# Microcontroller.net
KiCad netlist of a schematic drawn in Altium Designer
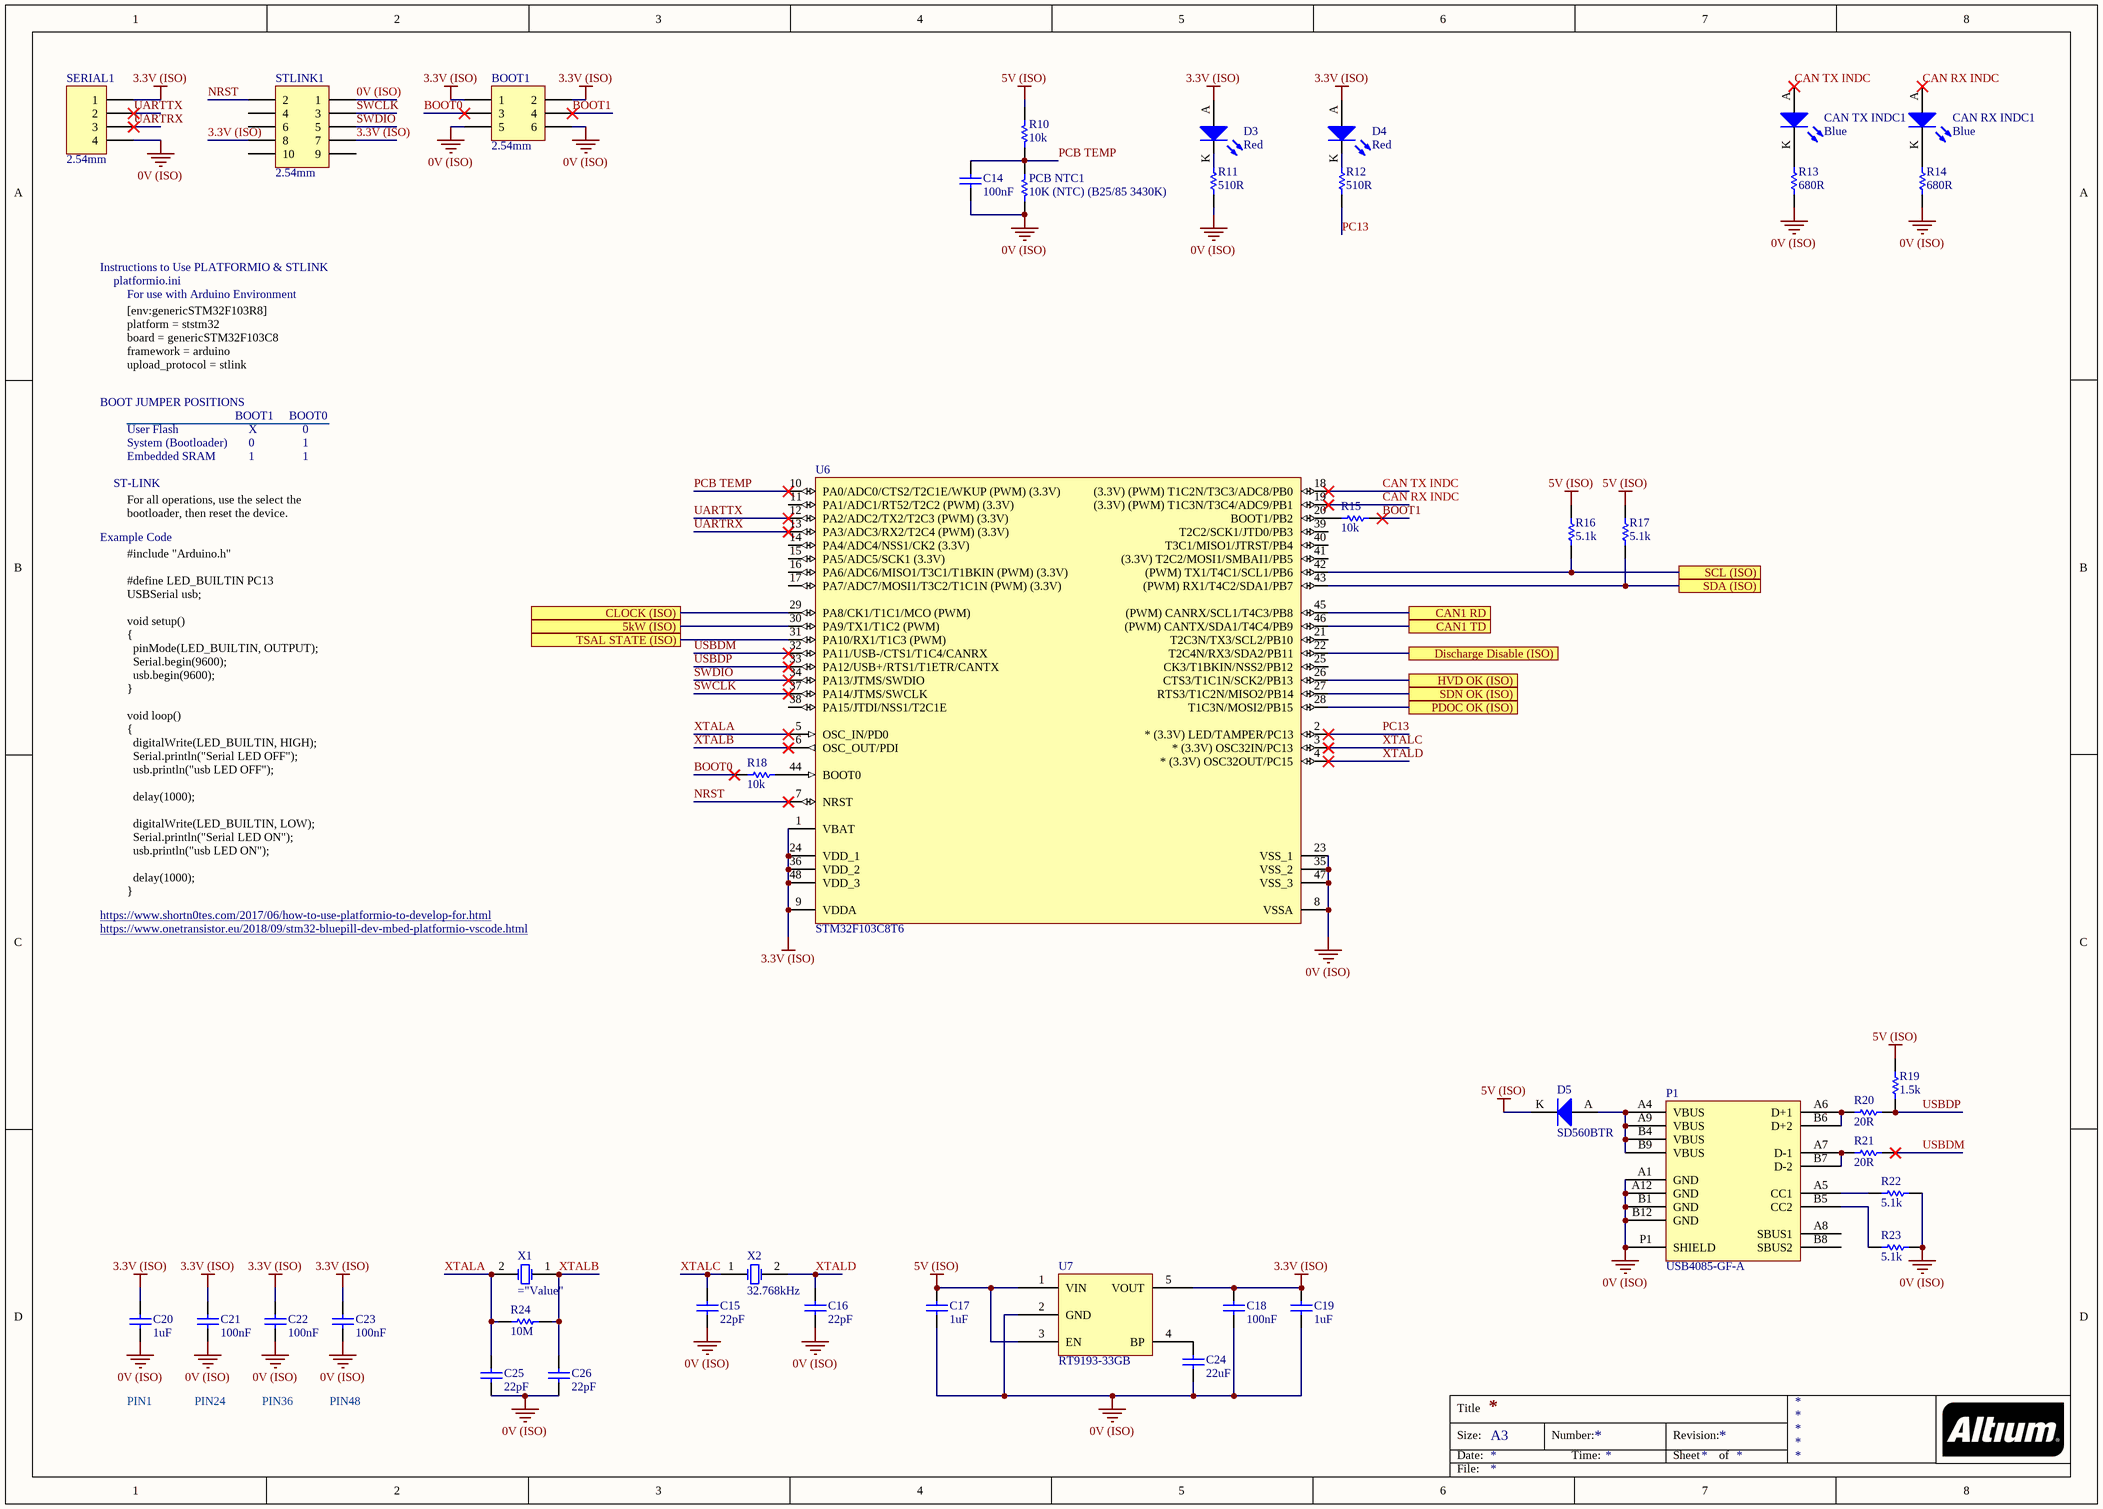
[diagram p0: Microcontroller.SchDoc]

(export (version "E")
  (design (tool "Eeschema 10.0.6"))
  (components
    (comp (ref "BOOT1")
      (value "2.54mm")
      (footprint "TH 2.54mm Header 2x3")
      (fields (field (name "PART NUMBER") "TH 2.54mm Header 2x3") (field (name "CONTACT") "NA"))
      (libsource (lib "ts_20-standard-connectors") (part "Header 2x3"))
    )
    (comp (ref "C14")
      (value "100nF")
      (footprint "0805")
      (fields
        (field (name "PART NUMBER") "GCM21BR71E104KA37L")
        (field (name "TOLERANCE") "10%")
        (field (name "MANUFACTURER") "muRata")
      )
      (libsource (lib "ts_20-standard-library") (part "Capacitor"))
    )
    (comp (ref "C15")
      (value "22pF")
      (footprint "0805")
      (fields
        (field (name "PART NUMBER") "GCM21B5C1H220JA37L")
        (field (name "TOLERANCE") "5%")
        (field (name "MANUFACTURER") "muRata")
      )
      (libsource (lib "ts_20-standard-library") (part "Capacitor"))
    )
    (comp (ref "C16")
      (value "22pF")
      (footprint "0805")
      (fields
        (field (name "PART NUMBER") "GCM21B5C1H220JA37L")
        (field (name "TOLERANCE") "5%")
        (field (name "MANUFACTURER") "muRata")
      )
      (libsource (lib "ts_20-standard-library") (part "Capacitor"))
    )
    (comp (ref "C17")
      (value "1uF")
      (footprint "0805")
      (fields
        (field (name "PART NUMBER") "AC0805KKX7R8BB105")
        (field (name "TOLERANCE") "10%")
        (field (name "MANUFACTURER") "YAGEO")
      )
      (libsource (lib "ts_20-standard-library") (part "Capacitor"))
    )
    (comp (ref "C18")
      (value "100nF")
      (footprint "0805")
      (fields
        (field (name "PART NUMBER") "GCM21BR71E104KA37L")
        (field (name "TOLERANCE") "10%")
        (field (name "MANUFACTURER") "muRata")
      )
      (libsource (lib "ts_20-standard-library") (part "Capacitor"))
    )
    (comp (ref "C19")
      (value "1uF")
      (footprint "0805")
      (fields
        (field (name "PART NUMBER") "AC0805KKX7R8BB105")
        (field (name "TOLERANCE") "10%")
        (field (name "MANUFACTURER") "YAGEO")
      )
      (libsource (lib "ts_20-standard-library") (part "Capacitor"))
    )
    (comp (ref "C20")
      (value "1uF")
      (footprint "0805")
      (fields
        (field (name "PART NUMBER") "AC0805KKX7R8BB105")
        (field (name "TOLERANCE") "10%")
        (field (name "MANUFACTURER") "YAGEO")
      )
      (libsource (lib "ts_20-standard-library") (part "Capacitor"))
    )
    (comp (ref "C21")
      (value "100nF")
      (footprint "0805")
      (fields
        (field (name "PART NUMBER") "GCM21BR71E104KA37L")
        (field (name "TOLERANCE") "10%")
        (field (name "MANUFACTURER") "muRata")
      )
      (libsource (lib "ts_20-standard-library") (part "Capacitor"))
    )
    (comp (ref "C22")
      (value "100nF")
      (footprint "0805")
      (fields
        (field (name "PART NUMBER") "GCM21BR71E104KA37L")
        (field (name "TOLERANCE") "10%")
        (field (name "MANUFACTURER") "muRata")
      )
      (libsource (lib "ts_20-standard-library") (part "Capacitor"))
    )
    (comp (ref "C23")
      (value "100nF")
      (footprint "0805")
      (fields
        (field (name "PART NUMBER") "GCM21BR71E104KA37L")
        (field (name "TOLERANCE") "10%")
        (field (name "MANUFACTURER") "muRata")
      )
      (libsource (lib "ts_20-standard-library") (part "Capacitor"))
    )
    (comp (ref "C24")
      (value "22uF")
      (footprint "0805")
      (fields
        (field (name "PART NUMBER") "GRM21BR61A226ME51L")
        (field (name "TOLERANCE") "20%")
        (field (name "MANUFACTURER") "muRata")
      )
      (libsource (lib "ts_20-standard-library") (part "Capacitor"))
    )
    (comp (ref "C25")
      (value "22pF")
      (footprint "0805")
      (fields
        (field (name "PART NUMBER") "GCM21B5C1H220JA37L")
        (field (name "TOLERANCE") "5%")
        (field (name "MANUFACTURER") "muRata")
      )
      (libsource (lib "ts_20-standard-library") (part "Capacitor"))
    )
    (comp (ref "C26")
      (value "22pF")
      (footprint "0805")
      (fields
        (field (name "PART NUMBER") "GCM21B5C1H220JA37L")
        (field (name "TOLERANCE") "5%")
        (field (name "MANUFACTURER") "muRata")
      )
      (libsource (lib "ts_20-standard-library") (part "Capacitor"))
    )
    (comp (ref "CAN RX INDC1")
      (value "Blue")
      (footprint "0805 LED")
      (description "LED BLUE CLEAR 2012 SMD")
      (fields
        (field (name "PART NUMBER") "SML-MN2BCTT86C")
        (field (name "MANUFACTURER") "ROHM Semiconductor")
      )
      (libsource (lib "ts_20-standard-library") (part "LED"))
    )
    (comp (ref "CAN TX INDC1")
      (value "Blue")
      (footprint "0805 LED")
      (description "LED BLUE CLEAR 2012 SMD")
      (fields
        (field (name "PART NUMBER") "SML-MN2BCTT86C")
        (field (name "MANUFACTURER") "ROHM Semiconductor")
      )
      (libsource (lib "ts_20-standard-library") (part "LED"))
    )
    (comp (ref "D3")
      (value "Red")
      (footprint "0805 LED")
      (description "Red LED Indication - Discrete 1.75V 0805 (2012 Metric)")
      (fields (field (name "MANUFACTURER") "ROHM Semiconductor") (field (name "PART NUMBER") "SML-210LTT86"))
      (libsource (lib "ts_20-standard-library") (part "LED"))
    )
    (comp (ref "D4")
      (value "Red")
      (footprint "0805 LED")
      (description "Red LED Indication - Discrete 1.75V 0805 (2012 Metric)")
      (fields (field (name "MANUFACTURER") "ROHM Semiconductor") (field (name "PART NUMBER") "SML-210LTT86"))
      (libsource (lib "ts_20-standard-library") (part "LED"))
    )
    (comp (ref "D5")
      (value "SD560BTR")
      (footprint "SMB Diode")
      (description "1.2V_F 600V 5A SMB")
      (fields
        (field (name "MANUFACTURER") "SMC Diode Solutions")
        (field (name "DIGIKEY PART NUMBER") "1655-1530-2-ND")
      )
      (libsource (lib "ts_20-standard-library") (part "Diode"))
    )
    (comp (ref "P1")
      (value "USB4085-GF-A")
      (footprint "USB4085-GF-A")
      (description "USB - C (Type - C) USB 2.0 Receptacle Connector 16 Position Through Hole, Right Angle")
      (fields (field (name "DIGIKEY PART NUMBER") "2073-USB4085-GF-ACT-ND"))
      (libsource (lib "ts_20-standard-connectors") (part "USB4085-GF-A"))
    )
    (comp (ref "PCB NTC1")
      (value "10K (NTC) (B25/85 3430K)")
      (footprint "0805")
      (fields
        (field (name "PART NUMBER") "NTCS0805E3103FLT")
        (field (name "MANUFACTURER") "Vishay Beyschlag")
        (field (name "TOLERANCE") "0.01")
      )
      (libsource (lib "ts_20-standard-library") (part "Resistor"))
    )
    (comp (ref "R10")
      (value "10k")
      (footprint "0805")
      (fields
        (field (name "PART NUMBER") "RC0805FR0710KL")
        (field (name "MANUFACTURER") "YAGEO")
        (field (name "TOLERANCE") "0.01")
      )
      (libsource (lib "ts_20-standard-library") (part "Resistor"))
    )
    (comp (ref "R11")
      (value "510R")
      (footprint "0805")
      (fields
        (field (name "MANUFACTURER") "YAGEO")
        (field (name "PART NUMBER") "RC0805FR07510RL")
        (field (name "TOLERANCE") "0.01")
      )
      (libsource (lib "ts_20-standard-library") (part "Resistor"))
    )
    (comp (ref "R12")
      (value "510R")
      (footprint "0805")
      (fields
        (field (name "MANUFACTURER") "YAGEO")
        (field (name "PART NUMBER") "RC0805FR07510RL")
        (field (name "TOLERANCE") "0.01")
      )
      (libsource (lib "ts_20-standard-library") (part "Resistor"))
    )
    (comp (ref "R13")
      (value "680R")
      (footprint "0805")
      (fields
        (field (name "PART NUMBER") "RC0805FR07680RL")
        (field (name "MANUFACTURER") "YAGEO")
        (field (name "TOLERANCE") "0.01")
      )
      (libsource (lib "ts_20-standard-library") (part "Resistor"))
    )
    (comp (ref "R14")
      (value "680R")
      (footprint "0805")
      (fields
        (field (name "PART NUMBER") "RC0805FR07680RL")
        (field (name "MANUFACTURER") "YAGEO")
        (field (name "TOLERANCE") "0.01")
      )
      (libsource (lib "ts_20-standard-library") (part "Resistor"))
    )
    (comp (ref "R15")
      (value "10k")
      (footprint "0805")
      (fields
        (field (name "PART NUMBER") "RC0805FR0710KL")
        (field (name "MANUFACTURER") "YAGEO")
        (field (name "TOLERANCE") "0.01")
      )
      (libsource (lib "ts_20-standard-library") (part "Resistor"))
    )
    (comp (ref "R16")
      (value "5.1k")
      (footprint "0805")
      (fields
        (field (name "PART NUMBER") "RC0805FR075K1L")
        (field (name "MANUFACTURER") "YAGEO")
        (field (name "TOLERANCE") "0.01")
      )
      (libsource (lib "ts_20-standard-library") (part "Resistor"))
    )
    (comp (ref "R17")
      (value "5.1k")
      (footprint "0805")
      (fields
        (field (name "PART NUMBER") "RC0805FR075K1L")
        (field (name "MANUFACTURER") "YAGEO")
        (field (name "TOLERANCE") "0.01")
      )
      (libsource (lib "ts_20-standard-library") (part "Resistor"))
    )
    (comp (ref "R18")
      (value "10k")
      (footprint "0805")
      (fields
        (field (name "PART NUMBER") "RC0805FR0710KL")
        (field (name "MANUFACTURER") "YAGEO")
        (field (name "TOLERANCE") "0.01")
      )
      (libsource (lib "ts_20-standard-library") (part "Resistor"))
    )
    (comp (ref "R19")
      (value "1.5k")
      (footprint "0805")
      (fields
        (field (name "PART NUMBER") "RC0805FR071K5L")
        (field (name "MANUFACTURER") "YAGEO")
        (field (name "TOLERANCE") "0.01")
      )
      (libsource (lib "ts_20-standard-library") (part "Resistor"))
    )
    (comp (ref "R20")
      (value "20R")
      (footprint "0805")
      (fields
        (field (name "PART NUMBER") "RC0805FR0720RL")
        (field (name "MANUFACTURER") "YAGEO")
        (field (name "TOLERANCE") "0.01")
      )
      (libsource (lib "ts_20-standard-library") (part "Resistor"))
    )
    (comp (ref "R21")
      (value "20R")
      (footprint "0805")
      (fields
        (field (name "PART NUMBER") "RC0805FR0720RL")
        (field (name "MANUFACTURER") "YAGEO")
        (field (name "TOLERANCE") "0.01")
      )
      (libsource (lib "ts_20-standard-library") (part "Resistor"))
    )
    (comp (ref "R22")
      (value "5.1k")
      (footprint "0805")
      (fields
        (field (name "PART NUMBER") "RC0805FR075K1L")
        (field (name "MANUFACTURER") "YAGEO")
        (field (name "TOLERANCE") "0.01")
      )
      (libsource (lib "ts_20-standard-library") (part "Resistor"))
    )
    (comp (ref "R23")
      (value "5.1k")
      (footprint "0805")
      (fields
        (field (name "PART NUMBER") "RC0805FR075K1L")
        (field (name "MANUFACTURER") "YAGEO")
        (field (name "TOLERANCE") "0.01")
      )
      (libsource (lib "ts_20-standard-library") (part "Resistor"))
    )
    (comp (ref "R24")
      (value "10M")
      (footprint "0805")
      (fields
        (field (name "PART NUMBER") "RC0805FR0710ML")
        (field (name "MANUFACTURER") "YAGEO")
        (field (name "TOLERANCE") "0.01")
      )
      (libsource (lib "ts_20-standard-library") (part "Resistor"))
    )
    (comp (ref "SERIAL1")
      (value "2.54mm")
      (footprint "TH 2.54mm Header 1x4")
      (fields (field (name "PART NUMBER") "TH 2.54mm Header 1x4") (field (name "CONTACT") "NA"))
      (libsource (lib "ts_20-standard-connectors") (part "Header 1x4"))
    )
    (comp (ref "STLINK1")
      (value "2.54mm")
      (footprint "TH 2.54mm Header 2x5")
      (fields (field (name "PART NUMBER") "TH 2.54mm Header 2x5") (field (name "CONTACT") "NA"))
      (libsource (lib "ts_20-standard-connectors") (part "Header 2x5"))
    )
    (comp (ref "U6")
      (value "STM32F103C8T6")
      (footprint "STM 48-LQFP")
      (description "ARM® Cortex®-M3 STM32F1 Microcontroller IC 32-Bit 72MHz 64KB (64K x 8) FLASH")
      (fields
        (field (name "MANUFACTURER") "STMicroelectronics")
        (field (name "DIGIKEY PART NUMBER") "497-6063-ND")
      )
      (libsource (lib "ts_20-standard-library") (part "STM32F103C8T6"))
    )
    (comp (ref "U7")
      (value "RT9193-33GB")
      (footprint "RICHTEK SOT-23-5")
      (description "IC REG LINEAR 3.3V 300MA SOT23-5")
      (fields (field (name "MANUFACTURER") "Richtek") (field (name "DIGIKEY PART NUMBER") "1028-1014-1-ND"))
      (libsource (lib "ts_20-standard-library") (part "RT9193-33GB"))
    )
    (comp (ref "X1")
      (value "~")
      (footprint "Abracon HC-49/US")
      (fields
        (field (name "PART NUMBER") "ABLS-16.000MHZ-B4-T")
        (field (name "MANUFACTURER") "Abracon LLC")
        (field (name "DIGIKEY PART NUMBER") "535-10226-1-ND")
      )
      (libsource (lib "ts_20-standard-library") (part "Crystal"))
    )
    (comp (ref "X2")
      (value "32.768kHz")
      (footprint "EPSON 2-SMD")
      (fields
        (field (name "PART NUMBER") "FC-135 32.7680KA-A5")
        (field (name "MANUFACTURER") "EPSON")
        (field (name "DIGIKEY PART NUMBER") "SER4103TR-ND")
      )
      (libsource (lib "ts_20-standard-library") (part "Crystal"))
    )
  )
  (nets
    (net (code "1") (name "/5kW (ISO)") (class "Default")
      (node (ref "U6") (pin "30") (pinfunction "PA9/TX1/T1C2_(PWM)_30") (pintype "bidirectional"))
    )
    (net (code "2") (name "/BOOT0") (class "Default")
      (node (ref "BOOT1") (pin "3") (pinfunction "3_3") (pintype "passive"))
      (node (ref "R18") (pin "1") (pinfunction "1_1") (pintype "passive"))
    )
    (net (code "3") (name "/BOOT1") (class "Default")
      (node (ref "BOOT1") (pin "4") (pinfunction "4_4") (pintype "passive"))
      (node (ref "R15") (pin "2") (pinfunction "2_2") (pintype "passive"))
    )
    (net (code "4") (name "/CAN RX INDC") (class "Default")
      (node (ref "CAN RX INDC1") (pin "A") (pinfunction "A_A") (pintype "passive"))
      (node (ref "U6") (pin "19") (pinfunction "(3.3V)_(PWM)_T1C3N/T3C4/ADC9/PB1_19") (pintype "bidirectional"))
    )
    (net (code "5") (name "/CAN TX INDC") (class "Default")
      (node (ref "CAN TX INDC1") (pin "A") (pinfunction "A_A") (pintype "passive"))
      (node (ref "U6") (pin "18") (pinfunction "(3.3V)_(PWM)_T1C2N/T3C3/ADC8/PB0_18") (pintype "bidirectional"))
    )
    (net (code "6") (name "/CAN1 RD") (class "Default")
      (node (ref "U6") (pin "45") (pinfunction "(PWM)_CANRX/SCL1/T4C3/PB8_45") (pintype "bidirectional"))
    )
    (net (code "7") (name "/CAN1 TD") (class "Default")
      (node (ref "U6") (pin "46") (pinfunction "(PWM)_CANTX/SDA1/T4C4/PB9_46") (pintype "bidirectional"))
    )
    (net (code "8") (name "/CLOCK (ISO)") (class "Default")
      (node (ref "U6") (pin "29") (pinfunction "PA8/CK1/T1C1/MCO_(PWM)_29") (pintype "bidirectional"))
    )
    (net (code "9") (name "/Discharge Disable (ISO)") (class "Default")
      (node (ref "U6") (pin "22") (pinfunction "T2C4N/RX3/SDA2/PB11_22") (pintype "bidirectional"))
    )
    (net (code "10") (name "/HVD OK (ISO)") (class "Default")
      (node (ref "U6") (pin "26") (pinfunction "CTS3/T1C1N/SCK2/PB13_26") (pintype "bidirectional"))
    )
    (net (code "11") (name "/NRST") (class "Default")
      (node (ref "STLINK1") (pin "2") (pinfunction "2_2") (pintype "passive"))
      (node (ref "U6") (pin "7") (pinfunction "NRST_7") (pintype "bidirectional"))
    )
    (net (code "12") (name "/PC13") (class "Default")
      (node (ref "R12") (pin "1") (pinfunction "1_1") (pintype "passive"))
      (node (ref "U6") (pin "2") (pinfunction "*_(3.3V)_LED/TAMPER/PC13_2") (pintype "bidirectional"))
    )
    (net (code "13") (name "/PCB TEMP") (class "Default")
      (node (ref "C14") (pin "2") (pinfunction "2_2") (pintype "passive"))
      (node (ref "PCB NTC1") (pin "2") (pinfunction "2_2") (pintype "passive"))
      (node (ref "R10") (pin "1") (pinfunction "1_1") (pintype "passive"))
      (node (ref "U6") (pin "10") (pinfunction "PA0/ADC0/CTS2/T2C1E/WKUP_(PWM)_(3.3V)_10") (pintype "bidirectional"))
    )
    (net (code "14") (name "/PDOC OK (ISO)") (class "Default")
      (node (ref "U6") (pin "28") (pinfunction "T1C3N/MOSI2/PB15_28") (pintype "bidirectional"))
    )
    (net (code "15") (name "/SCL (ISO)") (class "Default")
      (node (ref "R16") (pin "1") (pinfunction "1_1") (pintype "passive"))
      (node (ref "U6") (pin "42") (pinfunction "(PWM)_TX1/T4C1/SCL1/PB6_42") (pintype "bidirectional"))
    )
    (net (code "16") (name "/SDA (ISO)") (class "Default")
      (node (ref "R17") (pin "1") (pinfunction "1_1") (pintype "passive"))
      (node (ref "U6") (pin "43") (pinfunction "(PWM)_RX1/T4C2/SDA1/PB7_43") (pintype "bidirectional"))
    )
    (net (code "17") (name "/SDN OK (ISO)") (class "Default")
      (node (ref "U6") (pin "27") (pinfunction "RTS3/T1C2N/MISO2/PB14_27") (pintype "bidirectional"))
    )
    (net (code "18") (name "/SWCLK") (class "Default")
      (node (ref "STLINK1") (pin "3") (pinfunction "3_3") (pintype "passive"))
      (node (ref "U6") (pin "37") (pinfunction "PA14/JTMS/SWCLK_37") (pintype "bidirectional"))
    )
    (net (code "19") (name "/SWDIO") (class "Default")
      (node (ref "STLINK1") (pin "5") (pinfunction "5_5") (pintype "passive"))
      (node (ref "U6") (pin "34") (pinfunction "PA13/JTMS/SWDIO_34") (pintype "bidirectional"))
    )
    (net (code "20") (name "/TSAL STATE (ISO)") (class "Default")
      (node (ref "U6") (pin "31") (pinfunction "PA10/RX1/T1C3_(PWM)_31") (pintype "bidirectional"))
    )
    (net (code "21") (name "/UARTRX") (class "Default")
      (node (ref "SERIAL1") (pin "3") (pinfunction "3_3") (pintype "passive"))
      (node (ref "U6") (pin "13") (pinfunction "PA3/ADC3/RX2/T2C4_(PWM)_(3.3V)_13") (pintype "bidirectional"))
    )
    (net (code "22") (name "/UARTTX") (class "Default")
      (node (ref "SERIAL1") (pin "2") (pinfunction "2_2") (pintype "passive"))
      (node (ref "U6") (pin "12") (pinfunction "PA2/ADC2/TX2/T2C3_(PWM)_(3.3V)_12") (pintype "bidirectional"))
    )
    (net (code "23") (name "/USBDM") (class "Default")
      (node (ref "R21") (pin "2") (pinfunction "2_2") (pintype "passive"))
      (node (ref "U6") (pin "32") (pinfunction "PA11/USB-/CTS1/T1C4/CANRX_32") (pintype "bidirectional"))
    )
    (net (code "24") (name "/USBDP") (class "Default")
      (node (ref "R19") (pin "1") (pinfunction "1_1") (pintype "passive"))
      (node (ref "R20") (pin "2") (pinfunction "2_2") (pintype "passive"))
      (node (ref "U6") (pin "33") (pinfunction "PA12/USB+/RTS1/T1ETR/CANTX_33") (pintype "bidirectional"))
    )
    (net (code "25") (name "/XTALA") (class "Default")
      (node (ref "C25") (pin "2") (pinfunction "2_2") (pintype "passive"))
      (node (ref "R24") (pin "2") (pinfunction "2_2") (pintype "passive"))
      (node (ref "U6") (pin "5") (pinfunction "OSC_IN/PD0_5") (pintype "input"))
      (node (ref "X1") (pin "2") (pinfunction "OSC2_2") (pintype "passive"))
    )
    (net (code "26") (name "/XTALB") (class "Default")
      (node (ref "C26") (pin "2") (pinfunction "2_2") (pintype "passive"))
      (node (ref "R24") (pin "1") (pinfunction "1_1") (pintype "passive"))
      (node (ref "U6") (pin "6") (pinfunction "OSC_OUT/PDI_6") (pintype "output"))
      (node (ref "X1") (pin "1") (pinfunction "OSC1_1") (pintype "passive"))
    )
    (net (code "27") (name "/XTALC") (class "Default")
      (node (ref "C15") (pin "2") (pinfunction "2_2") (pintype "passive"))
      (node (ref "U6") (pin "3") (pinfunction "*_(3.3V)_OSC32IN/PC13_3") (pintype "bidirectional"))
      (node (ref "X2") (pin "1") (pinfunction "OSC1_1") (pintype "passive"))
    )
    (net (code "28") (name "/XTALD") (class "Default")
      (node (ref "C16") (pin "2") (pinfunction "2_2") (pintype "passive"))
      (node (ref "U6") (pin "4") (pinfunction "*_(3.3V)_OSC32OUT/PC15_4") (pintype "bidirectional"))
      (node (ref "X2") (pin "2") (pinfunction "OSC2_2") (pintype "passive"))
    )
    (net (code "29") (name "0V (ISO)") (class "Default")
      (node (ref "BOOT1") (pin "5") (pinfunction "5_5") (pintype "passive"))
      (node (ref "BOOT1") (pin "6") (pinfunction "6_6") (pintype "passive"))
      (node (ref "C14") (pin "1") (pinfunction "1_1") (pintype "passive"))
      (node (ref "C15") (pin "1") (pinfunction "1_1") (pintype "passive"))
      (node (ref "C16") (pin "1") (pinfunction "1_1") (pintype "passive"))
      (node (ref "C17") (pin "1") (pinfunction "1_1") (pintype "passive"))
      (node (ref "C18") (pin "1") (pinfunction "1_1") (pintype "passive"))
      (node (ref "C19") (pin "1") (pinfunction "1_1") (pintype "passive"))
      (node (ref "C20") (pin "1") (pinfunction "1_1") (pintype "passive"))
      (node (ref "C21") (pin "1") (pinfunction "1_1") (pintype "passive"))
      (node (ref "C22") (pin "1") (pinfunction "1_1") (pintype "passive"))
      (node (ref "C23") (pin "1") (pinfunction "1_1") (pintype "passive"))
      (node (ref "C24") (pin "1") (pinfunction "1_1") (pintype "passive"))
      (node (ref "C25") (pin "1") (pinfunction "1_1") (pintype "passive"))
      (node (ref "C26") (pin "1") (pinfunction "1_1") (pintype "passive"))
      (node (ref "P1") (pin "A1") (pinfunction "GND_A1") (pintype "passive"))
      (node (ref "P1") (pin "A12") (pinfunction "GND_A12") (pintype "passive"))
      (node (ref "P1") (pin "B1") (pinfunction "GND_B1") (pintype "passive"))
      (node (ref "P1") (pin "B12") (pinfunction "GND_B12") (pintype "passive"))
      (node (ref "P1") (pin "P1") (pinfunction "SHIELD_P1") (pintype "passive"))
      (node (ref "PCB NTC1") (pin "1") (pinfunction "1_1") (pintype "passive"))
      (node (ref "R11") (pin "1") (pinfunction "1_1") (pintype "passive"))
      (node (ref "R13") (pin "1") (pinfunction "1_1") (pintype "passive"))
      (node (ref "R14") (pin "1") (pinfunction "1_1") (pintype "passive"))
      (node (ref "R22") (pin "2") (pinfunction "2_2") (pintype "passive"))
      (node (ref "R23") (pin "2") (pinfunction "2_2") (pintype "passive"))
      (node (ref "SERIAL1") (pin "4") (pinfunction "4_4") (pintype "passive"))
      (node (ref "STLINK1") (pin "1") (pinfunction "1_1") (pintype "passive"))
      (node (ref "U6") (pin "23") (pinfunction "VSS_1_23") (pintype "power_in"))
      (node (ref "U6") (pin "35") (pinfunction "VSS_2_35") (pintype "power_in"))
      (node (ref "U6") (pin "47") (pinfunction "VSS_3_47") (pintype "power_in"))
      (node (ref "U6") (pin "8") (pinfunction "VSSA_8") (pintype "power_in"))
      (node (ref "U7") (pin "2") (pinfunction "GND_2") (pintype "passive"))
    )
    (net (code "30") (name "3.3V (ISO)") (class "Default")
      (node (ref "BOOT1") (pin "1") (pinfunction "1_1") (pintype "passive"))
      (node (ref "BOOT1") (pin "2") (pinfunction "2_2") (pintype "passive"))
      (node (ref "C18") (pin "2") (pinfunction "2_2") (pintype "passive"))
      (node (ref "C19") (pin "2") (pinfunction "2_2") (pintype "passive"))
      (node (ref "C20") (pin "2") (pinfunction "2_2") (pintype "passive"))
      (node (ref "C21") (pin "2") (pinfunction "2_2") (pintype "passive"))
      (node (ref "C22") (pin "2") (pinfunction "2_2") (pintype "passive"))
      (node (ref "C23") (pin "2") (pinfunction "2_2") (pintype "passive"))
      (node (ref "D3") (pin "A") (pinfunction "A_A") (pintype "passive"))
      (node (ref "D4") (pin "A") (pinfunction "A_A") (pintype "passive"))
      (node (ref "SERIAL1") (pin "1") (pinfunction "1_1") (pintype "passive"))
      (node (ref "STLINK1") (pin "7") (pinfunction "7_7") (pintype "passive"))
      (node (ref "STLINK1") (pin "8") (pinfunction "8_8") (pintype "passive"))
      (node (ref "U6") (pin "1") (pinfunction "VBAT_1") (pintype "power_in"))
      (node (ref "U6") (pin "24") (pinfunction "VDD_1_24") (pintype "power_in"))
      (node (ref "U6") (pin "36") (pinfunction "VDD_2_36") (pintype "power_in"))
      (node (ref "U6") (pin "48") (pinfunction "VDD_3_48") (pintype "power_in"))
      (node (ref "U6") (pin "9") (pinfunction "VDDA_9") (pintype "power_in"))
      (node (ref "U7") (pin "5") (pinfunction "VOUT_5") (pintype "passive"))
    )
    (net (code "31") (name "5V (ISO)") (class "Default")
      (node (ref "C17") (pin "2") (pinfunction "2_2") (pintype "passive"))
      (node (ref "D5") (pin "K") (pinfunction "K_K") (pintype "passive"))
      (node (ref "R10") (pin "2") (pinfunction "2_2") (pintype "passive"))
      (node (ref "R16") (pin "2") (pinfunction "2_2") (pintype "passive"))
      (node (ref "R17") (pin "2") (pinfunction "2_2") (pintype "passive"))
      (node (ref "R19") (pin "2") (pinfunction "2_2") (pintype "passive"))
      (node (ref "U7") (pin "1") (pinfunction "VIN_1") (pintype "passive"))
      (node (ref "U7") (pin "3") (pinfunction "EN_3") (pintype "passive"))
    )
    (net (code "32") (name "Net-(CAN RX INDC1-PadK)") (class "Default")
      (node (ref "CAN RX INDC1") (pin "K") (pinfunction "K_K") (pintype "passive"))
      (node (ref "R14") (pin "2") (pinfunction "2_2") (pintype "passive"))
    )
    (net (code "33") (name "Net-(CAN TX INDC1-PadK)") (class "Default")
      (node (ref "CAN TX INDC1") (pin "K") (pinfunction "K_K") (pintype "passive"))
      (node (ref "R13") (pin "2") (pinfunction "2_2") (pintype "passive"))
    )
    (net (code "34") (name "Net-(D3-PadK)") (class "Default")
      (node (ref "D3") (pin "K") (pinfunction "K_K") (pintype "passive"))
      (node (ref "R11") (pin "2") (pinfunction "2_2") (pintype "passive"))
    )
    (net (code "35") (name "Net-(D4-PadK)") (class "Default")
      (node (ref "D4") (pin "K") (pinfunction "K_K") (pintype "passive"))
      (node (ref "R12") (pin "2") (pinfunction "2_2") (pintype "passive"))
    )
    (net (code "36") (name "Net-(D5-PadA)") (class "Default")
      (node (ref "D5") (pin "A") (pinfunction "A_A") (pintype "passive"))
      (node (ref "P1") (pin "A4") (pinfunction "VBUS_A4") (pintype "passive"))
      (node (ref "P1") (pin "A9") (pinfunction "VBUS_A9") (pintype "passive"))
      (node (ref "P1") (pin "B4") (pinfunction "VBUS_B4") (pintype "passive"))
      (node (ref "P1") (pin "B9") (pinfunction "VBUS_B9") (pintype "passive"))
    )
    (net (code "37") (name "Net-(P1-CC1)") (class "Default")
      (node (ref "P1") (pin "A5") (pinfunction "CC1_A5") (pintype "passive"))
      (node (ref "R22") (pin "1") (pinfunction "1_1") (pintype "passive"))
    )
    (net (code "38") (name "Net-(P1-CC2)") (class "Default")
      (node (ref "P1") (pin "B5") (pinfunction "CC2_B5") (pintype "passive"))
      (node (ref "R23") (pin "1") (pinfunction "1_1") (pintype "passive"))
    )
    (net (code "39") (name "Net-(P1-D+1)") (class "Default")
      (node (ref "P1") (pin "A6") (pinfunction "D+1_A6") (pintype "passive"))
      (node (ref "P1") (pin "B6") (pinfunction "D+2_B6") (pintype "passive"))
      (node (ref "R20") (pin "1") (pinfunction "1_1") (pintype "passive"))
    )
    (net (code "40") (name "Net-(P1-D-1)") (class "Default")
      (node (ref "P1") (pin "A7") (pinfunction "D-1_A7") (pintype "passive"))
      (node (ref "P1") (pin "B7") (pinfunction "D-2_B7") (pintype "passive"))
      (node (ref "R21") (pin "1") (pinfunction "1_1") (pintype "passive"))
    )
    (net (code "41") (name "Net-(U6-BOOT0)") (class "Default")
      (node (ref "R18") (pin "2") (pinfunction "2_2") (pintype "passive"))
      (node (ref "U6") (pin "44") (pinfunction "BOOT0_44") (pintype "input"))
    )
    (net (code "42") (name "Net-(U6-BOOT1{slash}PB2)") (class "Default")
      (node (ref "R15") (pin "1") (pinfunction "1_1") (pintype "passive"))
      (node (ref "U6") (pin "20") (pinfunction "BOOT1/PB2_20") (pintype "bidirectional"))
    )
    (net (code "43") (name "Net-(U7-BP)") (class "Default")
      (node (ref "C24") (pin "2") (pinfunction "2_2") (pintype "passive"))
      (node (ref "U7") (pin "4") (pinfunction "BP_4") (pintype "passive"))
    )
    (net (code "44") (name "unconnected-(P1-SBUS1-PadA8)") (class "Default")
      (node (ref "P1") (pin "A8") (pinfunction "SBUS1_A8") (pintype "passive"))
    )
    (net (code "45") (name "unconnected-(P1-SBUS2-PadB8)") (class "Default")
      (node (ref "P1") (pin "B8") (pinfunction "SBUS2_B8") (pintype "passive"))
    )
    (net (code "46") (name "unconnected-(STLINK1-Pad4)") (class "Default")
      (node (ref "STLINK1") (pin "4") (pinfunction "4_4") (pintype "passive"))
    )
    (net (code "47") (name "unconnected-(STLINK1-Pad6)") (class "Default")
      (node (ref "STLINK1") (pin "6") (pinfunction "6_6") (pintype "passive"))
    )
    (net (code "48") (name "unconnected-(STLINK1-Pad9)") (class "Default")
      (node (ref "STLINK1") (pin "9") (pinfunction "9_9") (pintype "passive"))
    )
    (net (code "49") (name "unconnected-(STLINK1-Pad10)") (class "Default")
      (node (ref "STLINK1") (pin "10") (pinfunction "10_10") (pintype "passive"))
    )
    (net (code "50") (name "unconnected-(U6-(3.3V)_T2C2{slash}MOSI1{slash}SMBAI1{slash}PB5-Pad41)") (class "Default")
      (node (ref "U6") (pin "41") (pinfunction "(3.3V)_T2C2/MOSI1/SMBAI1/PB5_41") (pintype "bidirectional"))
    )
    (net (code "51") (name "unconnected-(U6-CK3{slash}T1BKIN{slash}NSS2{slash}PB12-Pad25)") (class "Default")
      (node (ref "U6") (pin "25") (pinfunction "CK3/T1BKIN/NSS2/PB12_25") (pintype "bidirectional"))
    )
    (net (code "52") (name "unconnected-(U6-PA1{slash}ADC1{slash}RT52{slash}T2C2_(PWM)_(3.3V)-Pad11)") (class "Default")
      (node (ref "U6") (pin "11") (pinfunction "PA1/ADC1/RT52/T2C2_(PWM)_(3.3V)_11") (pintype "bidirectional"))
    )
    (net (code "53") (name "unconnected-(U6-PA4{slash}ADC4{slash}NSS1{slash}CK2_(3.3V)-Pad14)") (class "Default")
      (node (ref "U6") (pin "14") (pinfunction "PA4/ADC4/NSS1/CK2_(3.3V)_14") (pintype "bidirectional"))
    )
    (net (code "54") (name "unconnected-(U6-PA5{slash}ADC5{slash}SCK1_(3.3V)-Pad15)") (class "Default")
      (node (ref "U6") (pin "15") (pinfunction "PA5/ADC5/SCK1_(3.3V)_15") (pintype "bidirectional"))
    )
    (net (code "55") (name "unconnected-(U6-PA6{slash}ADC6{slash}MISO1{slash}T3C1{slash}T1BKIN_(PWM)_(3.3V)-Pad16)") (class "Default")
      (node (ref "U6") (pin "16") (pinfunction "PA6/ADC6/MISO1/T3C1/T1BKIN_(PWM)_(3.3V)_16") (pintype "bidirectional"))
    )
    (net (code "56") (name "unconnected-(U6-PA7{slash}ADC7{slash}MOSI1{slash}T3C2{slash}T1C1N_(PWM)_(3.3V)-Pad17)") (class "Default")
      (node (ref "U6") (pin "17") (pinfunction "PA7/ADC7/MOSI1/T3C2/T1C1N_(PWM)_(3.3V)_17") (pintype "bidirectional"))
    )
    (net (code "57") (name "unconnected-(U6-PA15{slash}JTDI{slash}NSS1{slash}T2C1E-Pad38)") (class "Default")
      (node (ref "U6") (pin "38") (pinfunction "PA15/JTDI/NSS1/T2C1E_38") (pintype "bidirectional"))
    )
    (net (code "58") (name "unconnected-(U6-T2C2{slash}SCK1{slash}JTD0{slash}PB3-Pad39)") (class "Default")
      (node (ref "U6") (pin "39") (pinfunction "T2C2/SCK1/JTD0/PB3_39") (pintype "bidirectional"))
    )
    (net (code "59") (name "unconnected-(U6-T2C3N{slash}TX3{slash}SCL2{slash}PB10-Pad21)") (class "Default")
      (node (ref "U6") (pin "21") (pinfunction "T2C3N/TX3/SCL2/PB10_21") (pintype "bidirectional"))
    )
    (net (code "60") (name "unconnected-(U6-T3C1{slash}MISO1{slash}JTRST{slash}PB4-Pad40)") (class "Default")
      (node (ref "U6") (pin "40") (pinfunction "T3C1/MISO1/JTRST/PB4_40") (pintype "bidirectional"))
    )
  )
)
